# RollerShutterNode_rfm69_1-1.net
KiCad netlist of a schematic drawn in EAGLE
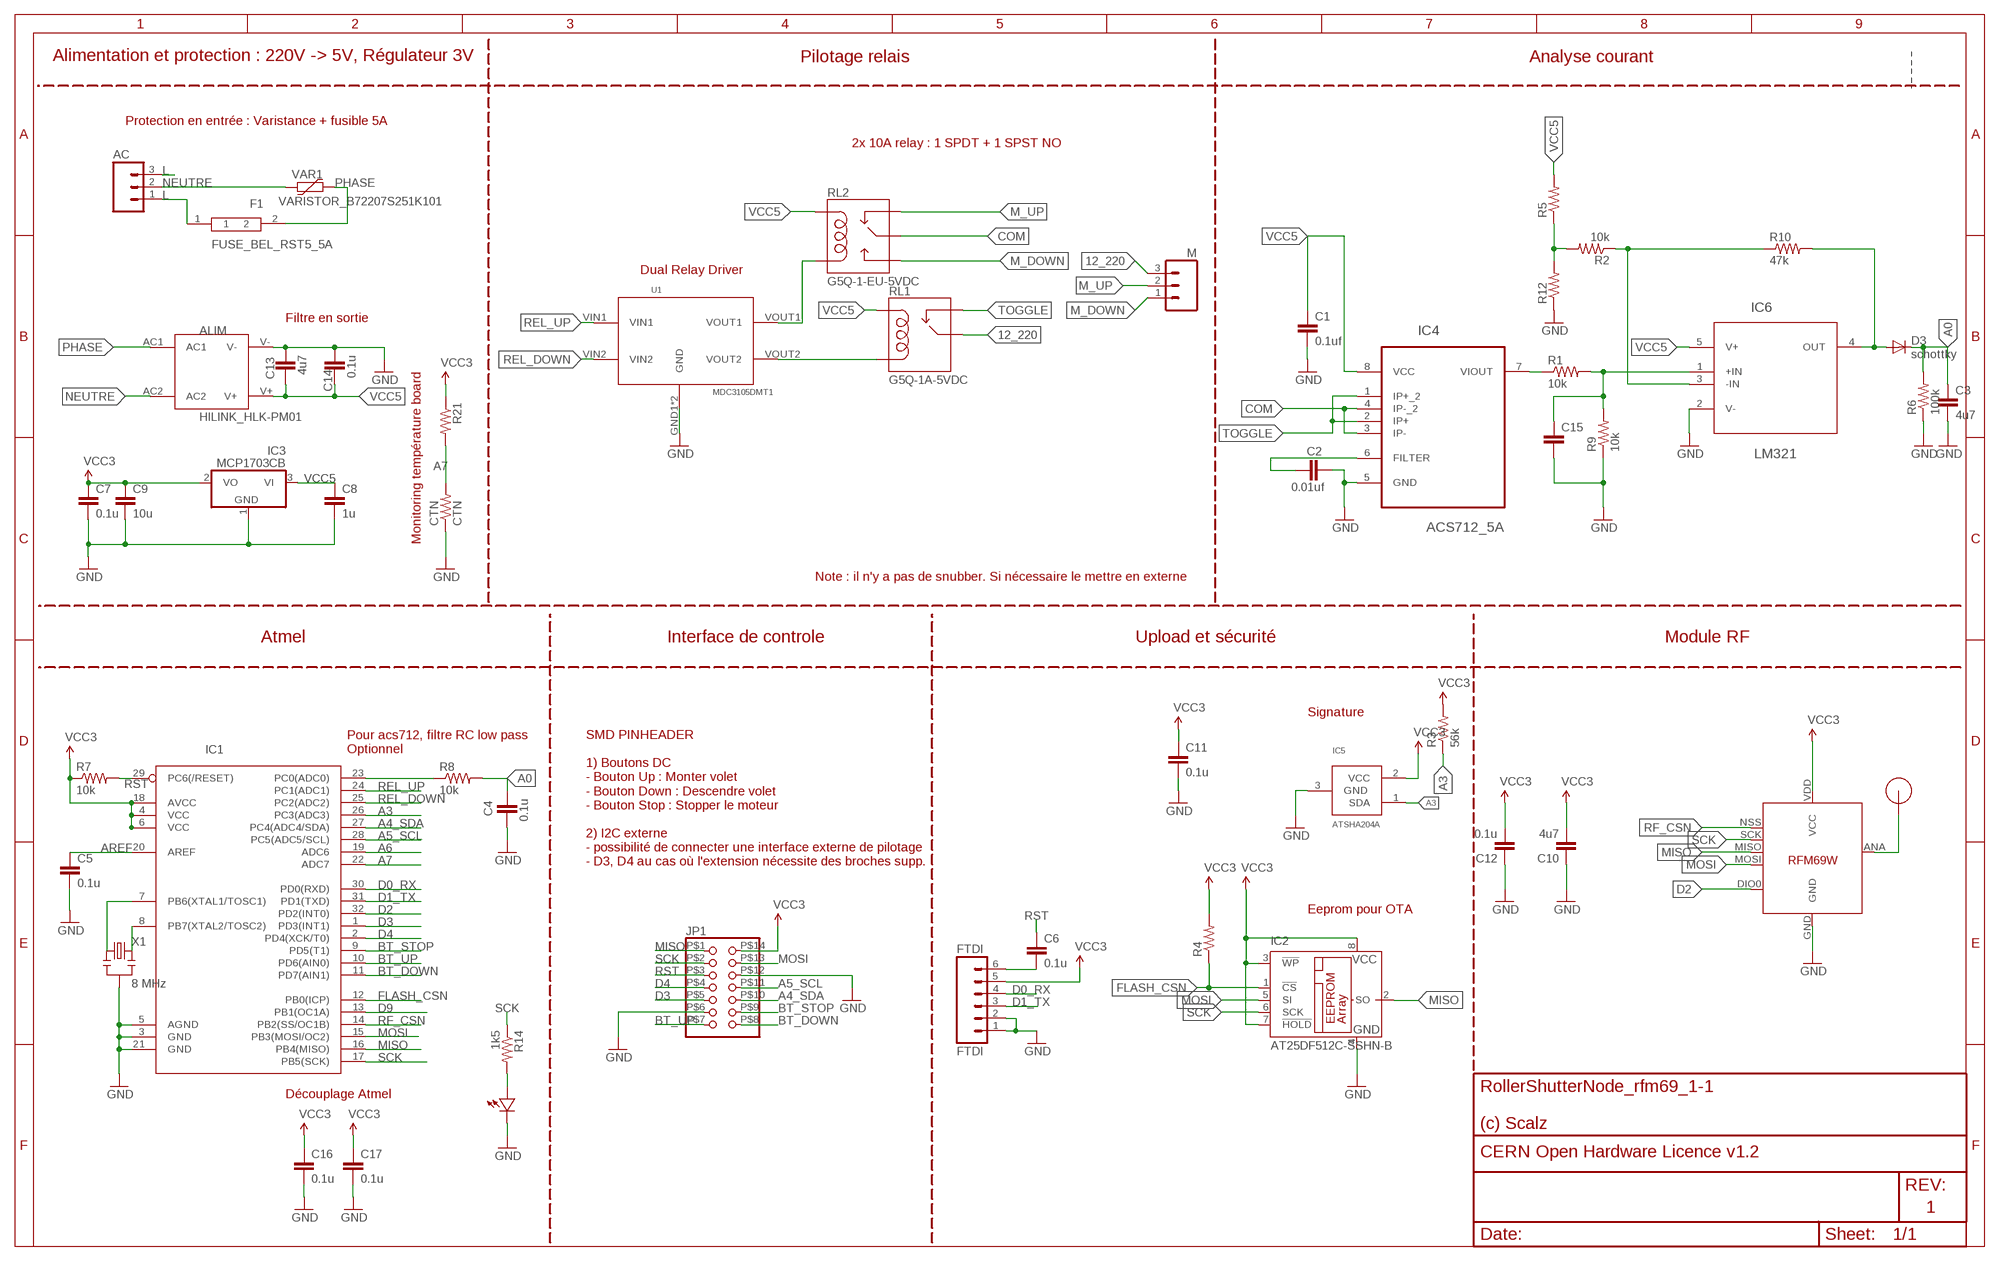
[diagram p0: schematic, sheet 1]

(export (version "E")
  (design (tool "Eeschema 10.0.6"))
  (components
    (comp (ref "AC")
      (value "M03-SCREW-5MM")
      (footprint "eagle-import:SCREWTERMINAL-5MM-3")
      (libsource (lib "eagle-import") (part "M03-SCREW-5MM"))
    )
    (comp (ref "ALIM")
      (value "HILINK_HLK-PM01")
      (footprint "eagle-import:HILINK_HLK-PM01")
      (libsource (lib "eagle-import") (part "HILINK_HLK-PM01"))
    )
    (comp (ref "ANT")
      (value "RFM12B_ANTENNA")
      (footprint "eagle-import:RFM12B-ANTENNA")
      (libsource (lib "eagle-import") (part "RFM12B_ANTENNA"))
    )
    (comp (ref "C1")
      (value "0.1uf")
      (footprint "eagle-import:0805-CAP")
      (libsource (lib "eagle-import") (part "CAP0805-CAP"))
    )
    (comp (ref "C2")
      (value "0.01uf")
      (footprint "eagle-import:0805-CAP")
      (libsource (lib "eagle-import") (part "CAP0805-CAP"))
    )
    (comp (ref "C3")
      (value "4u7")
      (footprint "eagle-import:0805-CAP")
      (libsource (lib "eagle-import") (part "CAP0805-CAP"))
    )
    (comp (ref "C4")
      (value "0.1u")
      (footprint "eagle-import:0805-CAP")
      (libsource (lib "eagle-import") (part "CAP0805-CAP"))
    )
    (comp (ref "C5")
      (value "0.1u")
      (footprint "eagle-import:0805-CAP")
      (libsource (lib "eagle-import") (part "CAP0805-CAP"))
    )
    (comp (ref "C6")
      (value "0.1u")
      (footprint "eagle-import:0805-CAP")
      (libsource (lib "eagle-import") (part "CAP0805-CAP"))
    )
    (comp (ref "C7")
      (value "0.1u")
      (footprint "eagle-import:0805-CAP")
      (libsource (lib "eagle-import") (part "CAP0805-CAP"))
    )
    (comp (ref "C8")
      (value "1u")
      (footprint "eagle-import:0805-CAP")
      (libsource (lib "eagle-import") (part "CAP0805-CAP"))
    )
    (comp (ref "C9")
      (value "10u")
      (footprint "eagle-import:0805-CAP")
      (libsource (lib "eagle-import") (part "CAP0805-CAP"))
    )
    (comp (ref "C10")
      (value "4u7")
      (footprint "eagle-import:0805-CAP")
      (libsource (lib "eagle-import") (part "CAP0805-CAP"))
    )
    (comp (ref "C11")
      (value "0.1u")
      (footprint "eagle-import:0805-CAP")
      (libsource (lib "eagle-import") (part "CAP0805-CAP"))
    )
    (comp (ref "C12")
      (value "0.1u")
      (footprint "eagle-import:0805-CAP")
      (libsource (lib "eagle-import") (part "CAP0805-CAP"))
    )
    (comp (ref "C13")
      (value "4u7")
      (footprint "eagle-import:0805-CAP")
      (libsource (lib "eagle-import") (part "CAP0805-CAP"))
    )
    (comp (ref "C14")
      (value "0.1u")
      (footprint "eagle-import:0805-CAP")
      (libsource (lib "eagle-import") (part "CAP0805-CAP"))
    )
    (comp (ref "C15")
      (value "CAP0805-CAP")
      (footprint "eagle-import:0805-CAP")
      (libsource (lib "eagle-import") (part "CAP0805-CAP"))
    )
    (comp (ref "C16")
      (value "0.1u")
      (footprint "eagle-import:0805-CAP")
      (libsource (lib "eagle-import") (part "CAP0805-CAP"))
    )
    (comp (ref "C17")
      (value "0.1u")
      (footprint "eagle-import:0805-CAP")
      (libsource (lib "eagle-import") (part "CAP0805-CAP"))
    )
    (comp (ref "CTN")
      (value "CTN")
      (footprint "eagle-import:0805-RES")
      (libsource (lib "eagle-import") (part "RESISTOR0805-RES"))
    )
    (comp (ref "D3")
      (value "schottky")
      (footprint "eagle-import:SOD-323")
      (libsource (lib "eagle-import") (part "DIODESOD"))
    )
    (comp (ref "D4")
      (value "LED0805")
      (footprint "eagle-import:0805-LED")
      (libsource (lib "eagle-import") (part "LED0805"))
    )
    (comp (ref "F1")
      (value "FUSE_BEL_RST5_5A")
      (footprint "eagle-import:FUSE_BEL_RST5_5A")
      (libsource (lib "eagle-import") (part "FUSE_BEL_RST5_5A"))
    )
    (comp (ref "FTDI")
      (value "FTDI")
      (footprint "eagle-import:1X06")
      (libsource (lib "eagle-import") (part "M06SIP"))
    )
    (comp (ref "IC1")
      (value "ATMega-328")
      (footprint "eagle-import:TQFP32-08")
      (libsource (lib "eagle-import") (part "ATMEGA168/328TQFP32"))
    )
    (comp (ref "IC2")
      (value "AT25DF512C-SSHN-B")
      (footprint "eagle-import:SO-08")
      (fields (field (name "MF") "MICROCHIP") (field (name "MPN") "25AA080/SN"))
      (libsource (lib "eagle-import") (part "25SNAA080"))
    )
    (comp (ref "IC3")
      (value "MCP1703CB")
      (footprint "eagle-import:SOT23")
      (libsource (lib "eagle-import") (part "MCP1703CB"))
    )
    (comp (ref "IC4")
      (value "ACS712_5A")
      (footprint "eagle-import:SOIC127P600X175-8N")
      (fields (field (name "MPN") "ACS712ELCTR-20A-T"))
      (libsource (lib "eagle-import") (part "ACS712ELCTR-20A-T"))
    )
    (comp (ref "IC5")
      (value "ATSHA204A")
      (footprint "eagle-import:SOT23")
      (libsource (lib "eagle-import") (part "ATSHA204A"))
    )
    (comp (ref "IC6")
      (value "LM321")
      (footprint "eagle-import:SOT95P285X120-5N")
      (fields (field (name "MPN") "LM321MF"))
      (libsource (lib "eagle-import") (part "LM321MF"))
    )
    (comp (ref "JP1")
      (value "PINHD-2X7")
      (footprint "eagle-import:2X07")
      (libsource (lib "eagle-import") (part "PINHD-2X7"))
    )
    (comp (ref "M")
      (value "M03-SCREW-5MM")
      (footprint "eagle-import:SCREWTERMINAL-5MM-3")
      (libsource (lib "eagle-import") (part "M03-SCREW-5MM"))
    )
    (comp (ref "R1")
      (value "10k")
      (footprint "eagle-import:0805-RES")
      (libsource (lib "eagle-import") (part "RESISTOR0805-RES"))
    )
    (comp (ref "R2")
      (value "10k")
      (footprint "eagle-import:0805-RES")
      (libsource (lib "eagle-import") (part "RESISTOR0805-RES"))
    )
    (comp (ref "R3")
      (value "56k")
      (footprint "eagle-import:0805-RES")
      (libsource (lib "eagle-import") (part "RESISTOR0805-RES"))
    )
    (comp (ref "R4")
      (value "RESISTOR0805-RES")
      (footprint "eagle-import:0805-RES")
      (libsource (lib "eagle-import") (part "RESISTOR0805-RES"))
    )
    (comp (ref "R5")
      (value "RESISTOR0805-RES")
      (footprint "eagle-import:0805-RES")
      (libsource (lib "eagle-import") (part "RESISTOR0805-RES"))
    )
    (comp (ref "R6")
      (value "100k")
      (footprint "eagle-import:0805-RES")
      (libsource (lib "eagle-import") (part "RESISTOR0805-RES"))
    )
    (comp (ref "R7")
      (value "10k")
      (footprint "eagle-import:0805-RES")
      (libsource (lib "eagle-import") (part "RESISTOR0805-RES"))
    )
    (comp (ref "R8")
      (value "10k")
      (footprint "eagle-import:0805-RES")
      (libsource (lib "eagle-import") (part "RESISTOR0805-RES"))
    )
    (comp (ref "R9")
      (value "10k")
      (footprint "eagle-import:0805-RES")
      (libsource (lib "eagle-import") (part "RESISTOR0805-RES"))
    )
    (comp (ref "R10")
      (value "47k")
      (footprint "eagle-import:0805-RES")
      (libsource (lib "eagle-import") (part "RESISTOR0805-RES"))
    )
    (comp (ref "R12")
      (value "RESISTOR0805-RES")
      (footprint "eagle-import:0805-RES")
      (libsource (lib "eagle-import") (part "RESISTOR0805-RES"))
    )
    (comp (ref "R14")
      (value "1k5")
      (footprint "eagle-import:0805-RES")
      (libsource (lib "eagle-import") (part "RESISTOR0805-RES"))
    )
    (comp (ref "R21")
      (value "RESISTOR0805-RES")
      (footprint "eagle-import:0805-RES")
      (libsource (lib "eagle-import") (part "RESISTOR0805-RES"))
    )
    (comp (ref "RFM69")
      (value "RFM69")
      (footprint "eagle-import:RFM69W-MINPADS")
      (libsource (lib "eagle-import") (part "RFM69"))
    )
    (comp (ref "RL1")
      (value "G5Q-1A-5VDC")
      (footprint "eagle-import:G5Q_SINGLE")
      (libsource (lib "eagle-import") (part "G5Q_SINGLE"))
    )
    (comp (ref "RL2")
      (value "G5Q-1-EU-5VDC")
      (footprint "eagle-import:RELAY-G5Q")
      (libsource (lib "eagle-import") (part "RELAYPTH"))
    )
    (comp (ref "U1")
      (value "MDC3105DMT1")
      (footprint "eagle-import:MDC3105DMT1")
      (libsource (lib "eagle-import") (part "MDC3105DMT1"))
    )
    (comp (ref "VAR1")
      (value "VARISTOR_B72207S251K101")
      (footprint "eagle-import:VARISTOR_B72207S251K101")
      (libsource (lib "eagle-import") (part "VARISTOR_B72207S251K101"))
    )
    (comp (ref "X1")
      (value "8 MHz")
      (footprint "eagle-import:RESONATOR-SMD")
      (libsource (lib "eagle-import") (part "RESONATORSMD"))
    )
  )
  (nets
    (net (code "1") (name "/A4_SDA") (class "Default")
      (node (ref "IC1") (pin "27") (pinfunction "PC4(ADC4/SDA)_27") (pintype "bidirectional"))
      (node (ref "JP1") (pin "P$10") (pinfunction "10_P$10") (pintype "passive"))
    )
    (net (code "2") (name "/A5_SCL") (class "Default")
      (node (ref "IC1") (pin "28") (pinfunction "PC5(ADC5/SCL)_28") (pintype "bidirectional"))
      (node (ref "JP1") (pin "P$11") (pinfunction "8_P$11") (pintype "passive"))
    )
    (net (code "3") (name "/A6") (class "Default")
      (node (ref "IC1") (pin "19") (pinfunction "ADC6_19") (pintype "bidirectional"))
    )
    (net (code "4") (name "/A7") (class "Default")
      (node (ref "CTN") (pin "2") (pinfunction "2_2") (pintype "passive"))
      (node (ref "IC1") (pin "22") (pinfunction "ADC7_22") (pintype "bidirectional"))
      (node (ref "R21") (pin "2") (pinfunction "2_2") (pintype "passive"))
    )
    (net (code "5") (name "/AREF") (class "Default")
      (node (ref "C5") (pin "1") (pinfunction "1_1") (pintype "passive"))
      (node (ref "IC1") (pin "20") (pinfunction "AREF_20") (pintype "bidirectional"))
    )
    (net (code "6") (name "/BT_DOWN") (class "Default")
      (node (ref "IC1") (pin "11") (pinfunction "PD7(AIN1)_11") (pintype "bidirectional"))
      (node (ref "JP1") (pin "P$8") (pinfunction "14_P$8") (pintype "passive"))
    )
    (net (code "7") (name "/BT_STOP") (class "Default")
      (node (ref "IC1") (pin "9") (pinfunction "PD5(T1)_9") (pintype "bidirectional"))
      (node (ref "JP1") (pin "P$9") (pinfunction "12_P$9") (pintype "passive"))
    )
    (net (code "8") (name "/BT_UP") (class "Default")
      (node (ref "IC1") (pin "10") (pinfunction "PD6(AIN0)_10") (pintype "bidirectional"))
      (node (ref "JP1") (pin "P$7") (pinfunction "13_P$7") (pintype "passive"))
    )
    (net (code "9") (name "/D0_RX") (class "Default")
      (node (ref "FTDI") (pin "4") (pinfunction "4_4") (pintype "passive"))
      (node (ref "IC1") (pin "30") (pinfunction "PD0(RXD)_30") (pintype "bidirectional"))
    )
    (net (code "10") (name "/D1_TX") (class "Default")
      (node (ref "FTDI") (pin "3") (pinfunction "3_3") (pintype "passive"))
      (node (ref "IC1") (pin "31") (pinfunction "PD1(TXD)_31") (pintype "bidirectional"))
    )
    (net (code "11") (name "/D3") (class "Default")
      (node (ref "IC1") (pin "1") (pinfunction "PD3(INT1)_1") (pintype "bidirectional"))
      (node (ref "JP1") (pin "P$5") (pinfunction "9_P$5") (pintype "passive"))
    )
    (net (code "12") (name "/D4") (class "Default")
      (node (ref "IC1") (pin "2") (pinfunction "PD4(XCK/T0)_2") (pintype "bidirectional"))
      (node (ref "JP1") (pin "P$4") (pinfunction "7_P$4") (pintype "passive"))
    )
    (net (code "13") (name "/D9") (class "Default")
      (node (ref "IC1") (pin "13") (pinfunction "PB1(OC1A)_13") (pintype "bidirectional"))
    )
    (net (code "14") (name "/L") (class "Default")
      (node (ref "AC") (pin "1") (pinfunction "1_1") (pintype "passive"))
      (node (ref "AC") (pin "3") (pinfunction "3_3") (pintype "passive"))
      (node (ref "F1") (pin "1") (pinfunction "1_1") (pintype "bidirectional"))
    )
    (net (code "15") (name "/RST") (class "Default")
      (node (ref "C6") (pin "1") (pinfunction "1_1") (pintype "passive"))
      (node (ref "IC1") (pin "29") (pinfunction "PC6(/RESET)_29") (pintype "bidirectional"))
      (node (ref "JP1") (pin "P$3") (pinfunction "5_P$3") (pintype "passive"))
      (node (ref "R7") (pin "2") (pinfunction "2_2") (pintype "passive"))
    )
    (net (code "16") (name "12_220") (class "Default")
      (node (ref "M") (pin "3") (pinfunction "3_3") (pintype "passive"))
      (node (ref "RL1") (pin "2") (pinfunction "MAIN_2") (pintype "bidirectional"))
    )
    (net (code "17") (name "A0") (class "Default")
      (node (ref "C3") (pin "1") (pinfunction "1_1") (pintype "passive"))
      (node (ref "C4") (pin "2") (pinfunction "2_2") (pintype "passive"))
      (node (ref "D3") (pin "1") (pinfunction "C_1") (pintype "passive"))
      (node (ref "R6") (pin "2") (pinfunction "2_2") (pintype "passive"))
      (node (ref "R8") (pin "2") (pinfunction "2_2") (pintype "passive"))
    )
    (net (code "18") (name "A3") (class "Default")
      (node (ref "IC1") (pin "26") (pinfunction "PC3(ADC3)_26") (pintype "bidirectional"))
      (node (ref "IC5") (pin "1") (pinfunction "SDA_1") (pintype "bidirectional"))
      (node (ref "R3") (pin "1") (pinfunction "1_1") (pintype "passive"))
    )
    (net (code "19") (name "COM") (class "Default")
      (node (ref "IC4") (pin "3") (pinfunction "IP-_3") (pintype "input"))
      (node (ref "IC4") (pin "4") (pinfunction "IP-_2_4") (pintype "input"))
      (node (ref "RL2") (pin "2") (pinfunction "MAIN_2") (pintype "bidirectional"))
    )
    (net (code "20") (name "D2") (class "Default")
      (node (ref "IC1") (pin "32") (pinfunction "PD2(INT0)_32") (pintype "bidirectional"))
      (node (ref "RFM69") (pin "DIO0") (pinfunction "DIO0_DIO0") (pintype "open_collector"))
    )
    (net (code "21") (name "FLASH_CSN") (class "Default")
      (node (ref "IC1") (pin "12") (pinfunction "PB0(ICP)_12") (pintype "bidirectional"))
      (node (ref "IC2") (pin "1") (pinfunction "~{CS}_1") (pintype "input"))
      (node (ref "R4") (pin "1") (pinfunction "1_1") (pintype "passive"))
    )
    (net (code "22") (name "GND") (class "Default")
      (node (ref "ALIM") (pin "V-") (pinfunction "V-_V-") (pintype "bidirectional"))
      (node (ref "C1") (pin "2") (pinfunction "2_2") (pintype "passive"))
      (node (ref "C10") (pin "1") (pinfunction "1_1") (pintype "passive"))
      (node (ref "C11") (pin "2") (pinfunction "2_2") (pintype "passive"))
      (node (ref "C12") (pin "1") (pinfunction "1_1") (pintype "passive"))
      (node (ref "C13") (pin "2") (pinfunction "2_2") (pintype "passive"))
      (node (ref "C14") (pin "2") (pinfunction "2_2") (pintype "passive"))
      (node (ref "C15") (pin "2") (pinfunction "2_2") (pintype "passive"))
      (node (ref "C16") (pin "2") (pinfunction "2_2") (pintype "passive"))
      (node (ref "C17") (pin "2") (pinfunction "2_2") (pintype "passive"))
      (node (ref "C2") (pin "2") (pinfunction "2_2") (pintype "passive"))
      (node (ref "C3") (pin "2") (pinfunction "2_2") (pintype "passive"))
      (node (ref "C4") (pin "1") (pinfunction "1_1") (pintype "passive"))
      (node (ref "C5") (pin "2") (pinfunction "2_2") (pintype "passive"))
      (node (ref "C7") (pin "2") (pinfunction "2_2") (pintype "passive"))
      (node (ref "C8") (pin "2") (pinfunction "2_2") (pintype "passive"))
      (node (ref "C9") (pin "2") (pinfunction "2_2") (pintype "passive"))
      (node (ref "CTN") (pin "1") (pinfunction "1_1") (pintype "passive"))
      (node (ref "D4") (pin "MINUS") (pinfunction "MINUS_MINUS") (pintype "passive"))
      (node (ref "FTDI") (pin "1") (pinfunction "1_1") (pintype "passive"))
      (node (ref "FTDI") (pin "2") (pinfunction "2_2") (pintype "passive"))
      (node (ref "IC1") (pin "21") (pinfunction "GND_21") (pintype "bidirectional"))
      (node (ref "IC1") (pin "3") (pinfunction "GND_3") (pintype "bidirectional"))
      (node (ref "IC1") (pin "5") (pinfunction "AGND_5") (pintype "bidirectional"))
      (node (ref "IC2") (pin "4") (pinfunction "GND_4") (pintype "power_in"))
      (node (ref "IC3") (pin "1") (pinfunction "GND_1") (pintype "passive"))
      (node (ref "IC4") (pin "5") (pinfunction "GND_5") (pintype "passive"))
      (node (ref "IC5") (pin "3") (pinfunction "GND_3") (pintype "bidirectional"))
      (node (ref "IC6") (pin "2") (pinfunction "V-_2") (pintype "power_in"))
      (node (ref "JP1") (pin "P$12") (pinfunction "6_P$12") (pintype "passive"))
      (node (ref "JP1") (pin "P$6") (pinfunction "11_P$6") (pintype "passive"))
      (node (ref "R12") (pin "1") (pinfunction "1_1") (pintype "passive"))
      (node (ref "R6") (pin "1") (pinfunction "1_1") (pintype "passive"))
      (node (ref "R9") (pin "1") (pinfunction "1_1") (pintype "passive"))
      (node (ref "RFM69") (pin "GND") (pinfunction "GND_GND") (pintype "power_in"))
      (node (ref "U1") (pin "GND1") (pinfunction "GND_GND1") (pintype "bidirectional"))
      (node (ref "U1") (pin "GND2") (pinfunction "GND_GND2") (pintype "bidirectional"))
      (node (ref "X1") (pin "2") (pinfunction "2_2") (pintype "passive"))
    )
    (net (code "23") (name "MISO") (class "Default")
      (node (ref "IC1") (pin "16") (pinfunction "PB4(MISO)_16") (pintype "bidirectional"))
      (node (ref "IC2") (pin "2") (pinfunction "SO_2") (pintype "bidirectional"))
      (node (ref "JP1") (pin "P$1") (pinfunction "1_P$1") (pintype "passive"))
      (node (ref "RFM69") (pin "MISO") (pinfunction "MISO_MISO") (pintype "input"))
    )
    (net (code "24") (name "MOSI") (class "Default")
      (node (ref "IC1") (pin "15") (pinfunction "PB3(MOSI/OC2)_15") (pintype "bidirectional"))
      (node (ref "IC2") (pin "5") (pinfunction "SI_5") (pintype "input"))
      (node (ref "JP1") (pin "P$13") (pinfunction "4_P$13") (pintype "passive"))
      (node (ref "RFM69") (pin "MOSI") (pinfunction "MOSI_MOSI") (pintype "output"))
    )
    (net (code "25") (name "M_DOWN") (class "Default")
      (node (ref "M") (pin "1") (pinfunction "1_1") (pintype "passive"))
      (node (ref "RL2") (pin "3") (pinfunction "NO_3") (pintype "bidirectional"))
    )
    (net (code "26") (name "M_UP") (class "Default")
      (node (ref "M") (pin "2") (pinfunction "2_2") (pintype "passive"))
      (node (ref "RL2") (pin "4") (pinfunction "NC_4") (pintype "bidirectional"))
    )
    (net (code "27") (name "NEUTRE") (class "Default")
      (node (ref "AC") (pin "2") (pinfunction "2_2") (pintype "passive"))
      (node (ref "ALIM") (pin "AC2") (pinfunction "AC2_AC2") (pintype "bidirectional"))
      (node (ref "VAR1") (pin "1") (pinfunction "1_1") (pintype "passive"))
    )
    (net (code "28") (name "Net-(ANT-1)") (class "Default")
      (node (ref "ANT") (pin "P$1") (pinfunction "1_P$1") (pintype "bidirectional"))
      (node (ref "RFM69") (pin "ANA") (pinfunction "ANT_ANA") (pintype "passive"))
    )
    (net (code "29") (name "Net-(C6-Pad2)") (class "Default")
      (node (ref "C6") (pin "2") (pinfunction "2_2") (pintype "passive"))
      (node (ref "FTDI") (pin "6") (pinfunction "6_6") (pintype "passive"))
    )
    (net (code "30") (name "Net-(D3-A)") (class "Default")
      (node (ref "D3") (pin "2") (pinfunction "A_2") (pintype "passive"))
      (node (ref "IC6") (pin "4") (pinfunction "OUT_4") (pintype "output"))
      (node (ref "R10") (pin "2") (pinfunction "2_2") (pintype "passive"))
    )
    (net (code "31") (name "Net-(D4-PadPLUS)") (class "Default")
      (node (ref "D4") (pin "PLUS") (pinfunction "PLUS_PLUS") (pintype "passive"))
      (node (ref "R14") (pin "2") (pinfunction "2_2") (pintype "passive"))
    )
    (net (code "32") (name "Net-(IC1-PB6(XTAL1{slash}TOSC1))") (class "Default")
      (node (ref "IC1") (pin "7") (pinfunction "PB6(XTAL1/TOSC1)_7") (pintype "bidirectional"))
      (node (ref "X1") (pin "1") (pinfunction "1_1") (pintype "passive"))
    )
    (net (code "33") (name "Net-(IC1-PB7(XTAL2{slash}TOSC2))") (class "Default")
      (node (ref "IC1") (pin "8") (pinfunction "PB7(XTAL2/TOSC2)_8") (pintype "bidirectional"))
      (node (ref "X1") (pin "3") (pinfunction "3_3") (pintype "passive"))
    )
    (net (code "34") (name "Net-(IC1-PC0(ADC0))") (class "Default")
      (node (ref "IC1") (pin "23") (pinfunction "PC0(ADC0)_23") (pintype "bidirectional"))
      (node (ref "R8") (pin "1") (pinfunction "1_1") (pintype "passive"))
    )
    (net (code "35") (name "Net-(IC4-FILTER)") (class "Default")
      (node (ref "C2") (pin "1") (pinfunction "1_1") (pintype "passive"))
      (node (ref "IC4") (pin "6") (pinfunction "FILTER_6") (pintype "input"))
    )
    (net (code "36") (name "Net-(IC4-VIOUT)") (class "Default")
      (node (ref "IC4") (pin "7") (pinfunction "VIOUT_7") (pintype "output"))
      (node (ref "R1") (pin "1") (pinfunction "1_1") (pintype "passive"))
    )
    (net (code "37") (name "Net-(IC6-+IN)") (class "Default")
      (node (ref "C15") (pin "1") (pinfunction "1_1") (pintype "passive"))
      (node (ref "IC6") (pin "1") (pinfunction "+IN_1") (pintype "input"))
      (node (ref "R1") (pin "2") (pinfunction "2_2") (pintype "passive"))
      (node (ref "R9") (pin "2") (pinfunction "2_2") (pintype "passive"))
    )
    (net (code "38") (name "Net-(IC6--IN)") (class "Default")
      (node (ref "IC6") (pin "3") (pinfunction "-IN_3") (pintype "input"))
      (node (ref "R10") (pin "1") (pinfunction "1_1") (pintype "passive"))
      (node (ref "R2") (pin "1") (pinfunction "1_1") (pintype "passive"))
    )
    (net (code "39") (name "Net-(R12-Pad2)") (class "Default")
      (node (ref "R12") (pin "2") (pinfunction "2_2") (pintype "passive"))
      (node (ref "R2") (pin "2") (pinfunction "2_2") (pintype "passive"))
      (node (ref "R5") (pin "1") (pinfunction "1_1") (pintype "passive"))
    )
    (net (code "40") (name "Net-(RL1-COIL2)") (class "Default")
      (node (ref "RL1") (pin "5") (pinfunction "COIL2_5") (pintype "bidirectional"))
      (node (ref "U1") (pin "VOUT2") (pinfunction "VOUT2_VOUT2") (pintype "bidirectional"))
    )
    (net (code "41") (name "Net-(RL2-COIL2)") (class "Default")
      (node (ref "RL2") (pin "1") (pinfunction "COIL2_1") (pintype "bidirectional"))
      (node (ref "U1") (pin "VOUT1") (pinfunction "VOUT1_VOUT1") (pintype "bidirectional"))
    )
    (net (code "42") (name "PHASE") (class "Default")
      (node (ref "ALIM") (pin "AC1") (pinfunction "AC1_AC1") (pintype "bidirectional"))
      (node (ref "F1") (pin "2") (pinfunction "2_2") (pintype "bidirectional"))
      (node (ref "VAR1") (pin "2") (pinfunction "2_2") (pintype "passive"))
    )
    (net (code "43") (name "REL_DOWN") (class "Default")
      (node (ref "IC1") (pin "25") (pinfunction "PC2(ADC2)_25") (pintype "bidirectional"))
      (node (ref "U1") (pin "VIN2") (pinfunction "VIN2_VIN2") (pintype "bidirectional"))
    )
    (net (code "44") (name "REL_UP") (class "Default")
      (node (ref "IC1") (pin "24") (pinfunction "PC1(ADC1)_24") (pintype "bidirectional"))
      (node (ref "U1") (pin "VIN1") (pinfunction "VIN1_VIN1") (pintype "bidirectional"))
    )
    (net (code "45") (name "RF_CSN") (class "Default")
      (node (ref "IC1") (pin "14") (pinfunction "PB2(SS/OC1B)_14") (pintype "bidirectional"))
      (node (ref "RFM69") (pin "NSS") (pinfunction "SEL_NSS") (pintype "input"))
    )
    (net (code "46") (name "SCK") (class "Default")
      (node (ref "IC1") (pin "17") (pinfunction "PB5(SCK)_17") (pintype "bidirectional"))
      (node (ref "IC2") (pin "6") (pinfunction "SCK_6") (pintype "input"))
      (node (ref "JP1") (pin "P$2") (pinfunction "3_P$2") (pintype "passive"))
      (node (ref "R14") (pin "1") (pinfunction "1_1") (pintype "passive"))
      (node (ref "RFM69") (pin "SCK") (pinfunction "SCK_SCK") (pintype "input"))
    )
    (net (code "47") (name "TOGGLE") (class "Default")
      (node (ref "IC4") (pin "1") (pinfunction "IP+_2_1") (pintype "input"))
      (node (ref "IC4") (pin "2") (pinfunction "IP+_2") (pintype "input"))
      (node (ref "RL1") (pin "3") (pinfunction "NC_3") (pintype "bidirectional"))
    )
    (net (code "48") (name "VCC3") (class "Default")
      (node (ref "C10") (pin "2") (pinfunction "2_2") (pintype "passive"))
      (node (ref "C11") (pin "1") (pinfunction "1_1") (pintype "passive"))
      (node (ref "C12") (pin "2") (pinfunction "2_2") (pintype "passive"))
      (node (ref "C16") (pin "1") (pinfunction "1_1") (pintype "passive"))
      (node (ref "C17") (pin "1") (pinfunction "1_1") (pintype "passive"))
      (node (ref "C7") (pin "1") (pinfunction "1_1") (pintype "passive"))
      (node (ref "C9") (pin "1") (pinfunction "1_1") (pintype "passive"))
      (node (ref "FTDI") (pin "5") (pinfunction "5_5") (pintype "passive"))
      (node (ref "IC1") (pin "18") (pinfunction "AVCC_18") (pintype "bidirectional"))
      (node (ref "IC1") (pin "4") (pinfunction "VCC_4") (pintype "bidirectional"))
      (node (ref "IC1") (pin "6") (pinfunction "VCC_6") (pintype "bidirectional"))
      (node (ref "IC2") (pin "3") (pinfunction "~{WP}_3") (pintype "input"))
      (node (ref "IC2") (pin "7") (pinfunction "~{HOLD}_7") (pintype "input"))
      (node (ref "IC2") (pin "8") (pinfunction "VCC_8") (pintype "power_in"))
      (node (ref "IC3") (pin "2") (pinfunction "VO_2") (pintype "passive"))
      (node (ref "IC5") (pin "2") (pinfunction "VCC_2") (pintype "bidirectional"))
      (node (ref "JP1") (pin "P$14") (pinfunction "2_P$14") (pintype "passive"))
      (node (ref "R21") (pin "1") (pinfunction "1_1") (pintype "passive"))
      (node (ref "R3") (pin "2") (pinfunction "2_2") (pintype "passive"))
      (node (ref "R4") (pin "2") (pinfunction "2_2") (pintype "passive"))
      (node (ref "R7") (pin "1") (pinfunction "1_1") (pintype "passive"))
      (node (ref "RFM69") (pin "VDD") (pinfunction "VCC_VDD") (pintype "power_in"))
    )
    (net (code "49") (name "VCC5") (class "Default")
      (node (ref "ALIM") (pin "V+") (pinfunction "V+_V+") (pintype "bidirectional"))
      (node (ref "C1") (pin "1") (pinfunction "1_1") (pintype "passive"))
      (node (ref "C13") (pin "1") (pinfunction "1_1") (pintype "passive"))
      (node (ref "C14") (pin "1") (pinfunction "1_1") (pintype "passive"))
      (node (ref "C8") (pin "1") (pinfunction "1_1") (pintype "passive"))
      (node (ref "IC3") (pin "3") (pinfunction "VI_3") (pintype "input"))
      (node (ref "IC4") (pin "8") (pinfunction "VCC_8") (pintype "power_in"))
      (node (ref "IC6") (pin "5") (pinfunction "V+_5") (pintype "power_in"))
      (node (ref "R5") (pin "2") (pinfunction "2_2") (pintype "passive"))
      (node (ref "RL1") (pin "1") (pinfunction "COIL1_1") (pintype "bidirectional"))
      (node (ref "RL2") (pin "5") (pinfunction "COIL1_5") (pintype "bidirectional"))
    )
  )
)
